# power_pcb.net
KiCad netlist of a schematic drawn in EAGLE
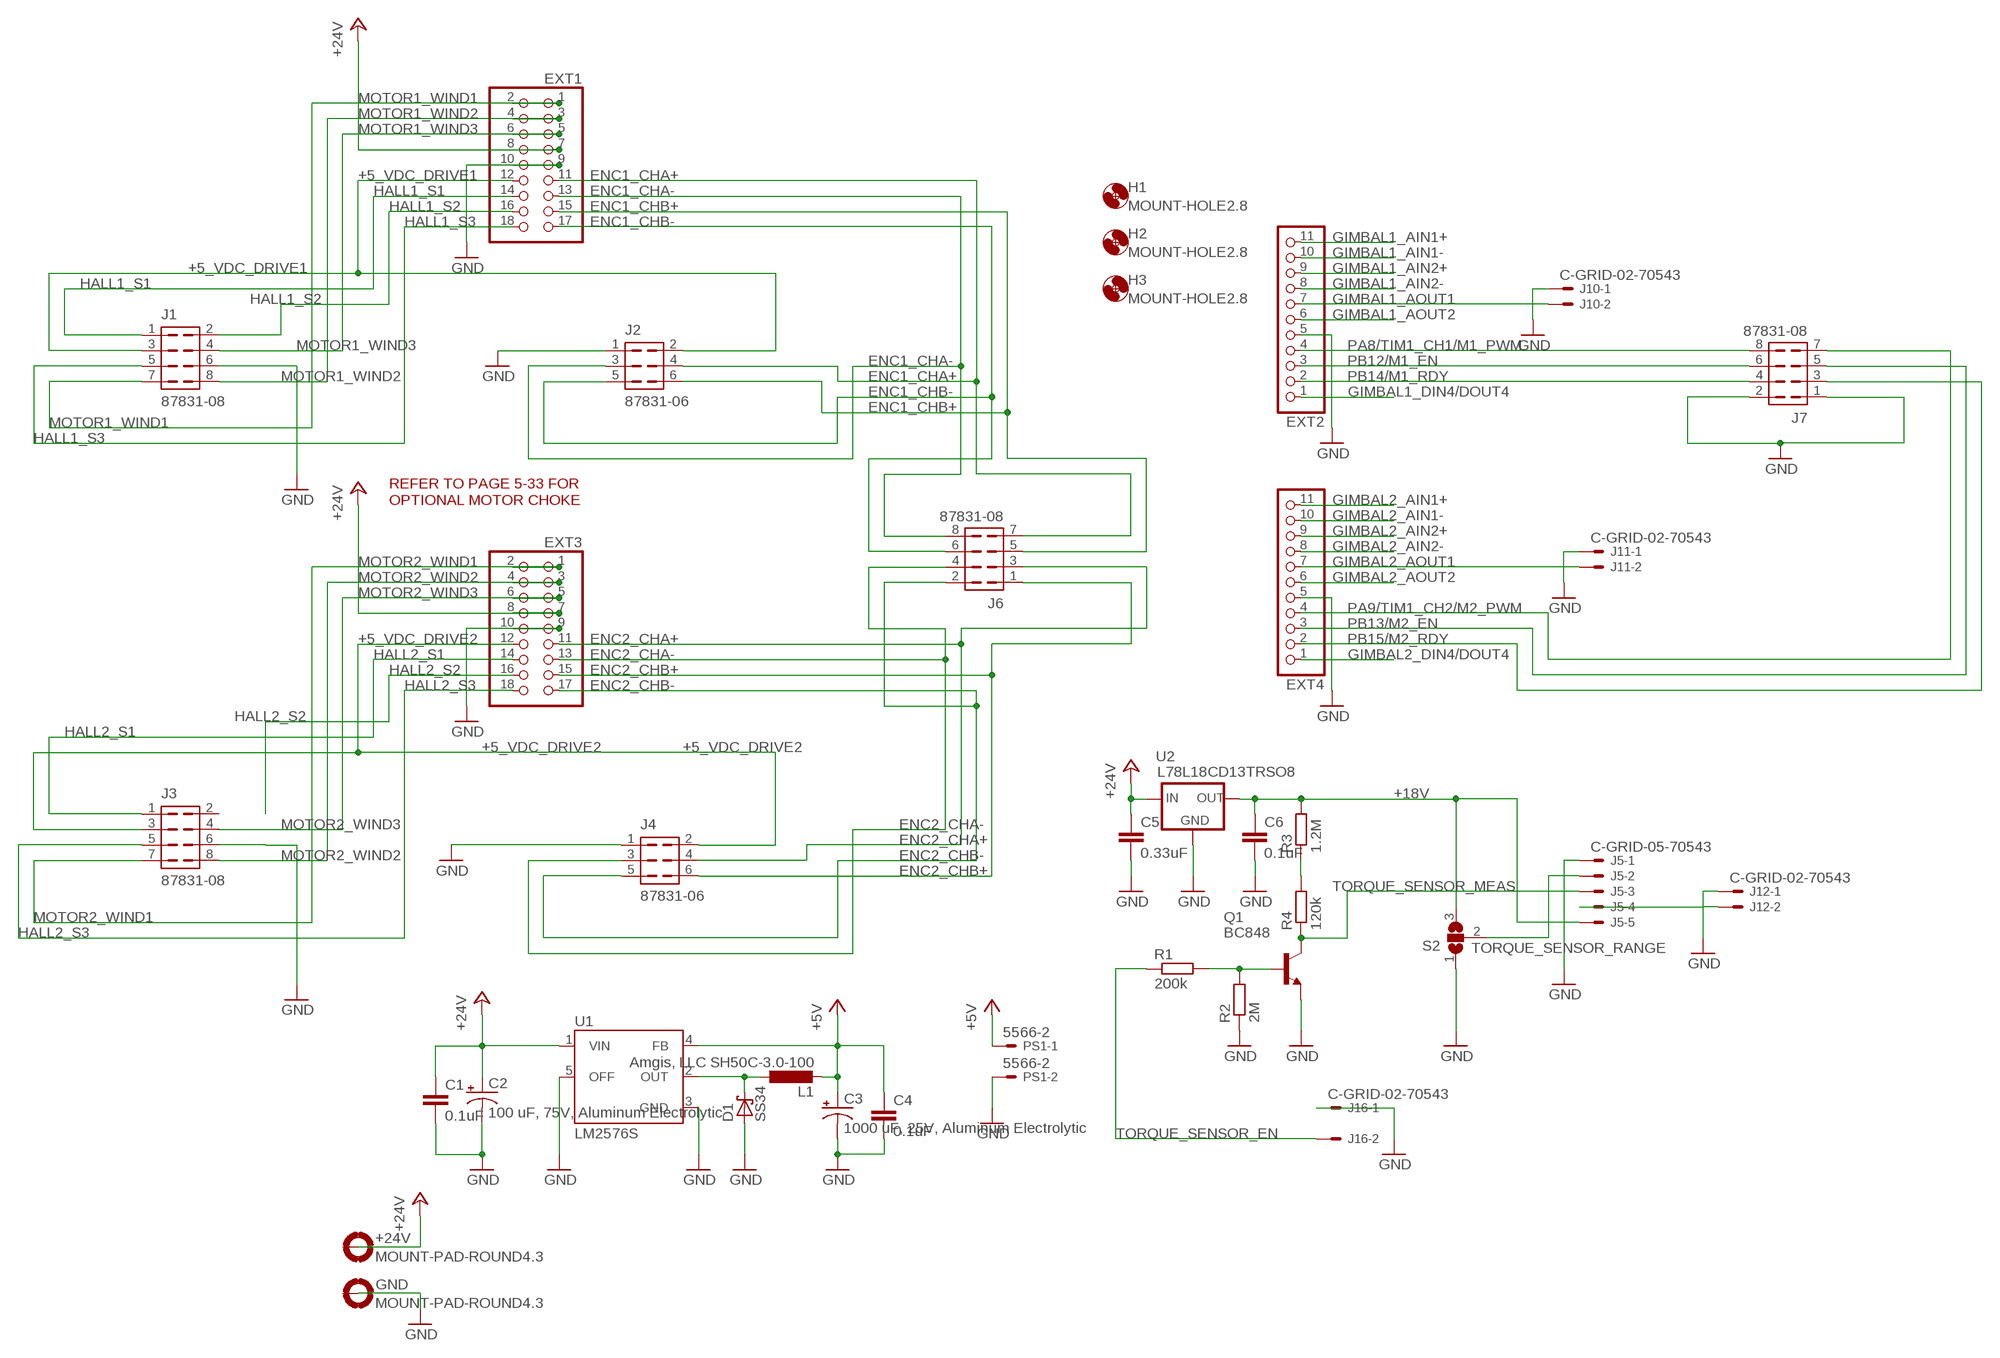
[diagram p0: schematic, sheet 1]

(export (version "E")
  (design (tool "Eeschema 10.0.6"))
  (components
    (comp (ref "+24V")
      (value "MOUNT-PAD-ROUND4.3")
      (footprint "eagle-import:4,3-PAD")
      (libsource (lib "eagle-import") (part "MOUNT-PAD-ROUND4.3"))
    )
    (comp (ref "C1")
      (value "0.1uF")
      (footprint "eagle-import:C0603")
      (libsource (lib "eagle-import") (part "C-EUC0603"))
    )
    (comp (ref "C2")
      (value "100 uF, 75V, Aluminum Electrolytic")
      (footprint "eagle-import:PANASONIC_H13")
      (libsource (lib "eagle-import") (part "CAP_POLH13"))
    )
    (comp (ref "C3")
      (value "1000 uF, 25V, Aluminum Electrolytic")
      (footprint "eagle-import:PANASONIC_H13")
      (libsource (lib "eagle-import") (part "CAP_POLH13"))
    )
    (comp (ref "C4")
      (value "0.1uF")
      (footprint "eagle-import:C0603")
      (libsource (lib "eagle-import") (part "C-EUC0603"))
    )
    (comp (ref "C5")
      (value "0.33uF")
      (footprint "eagle-import:C0603")
      (libsource (lib "eagle-import") (part "C-EUC0603"))
    )
    (comp (ref "C6")
      (value "0.1uF")
      (footprint "eagle-import:C0603")
      (libsource (lib "eagle-import") (part "C-EUC0603"))
    )
    (comp (ref "D1")
      (value "SS34")
      (footprint "eagle-import:SMC")
      (libsource (lib "eagle-import") (part "SCHOTTKY-DIODESMC"))
    )
    (comp (ref "EXT1")
      (value "PINHD-2X9")
      (footprint "eagle-import:2X09")
      (libsource (lib "eagle-import") (part "PINHD-2X9"))
    )
    (comp (ref "EXT2")
      (value "PINHD-1X11")
      (footprint "eagle-import:1X11")
      (libsource (lib "eagle-import") (part "PINHD-1X11"))
    )
    (comp (ref "EXT3")
      (value "PINHD-2X9")
      (footprint "eagle-import:2X09")
      (libsource (lib "eagle-import") (part "PINHD-2X9"))
    )
    (comp (ref "EXT4")
      (value "PINHD-1X11")
      (footprint "eagle-import:1X11")
      (libsource (lib "eagle-import") (part "PINHD-1X11"))
    )
    (comp (ref "GND")
      (value "MOUNT-PAD-ROUND4.3")
      (footprint "eagle-import:4,3-PAD")
      (libsource (lib "eagle-import") (part "MOUNT-PAD-ROUND4.3"))
    )
    (comp (ref "H1")
      (value "MOUNT-HOLE2.8")
      (footprint "eagle-import:2,8")
      (libsource (lib "eagle-import") (part "MOUNT-HOLE2.8"))
    )
    (comp (ref "H2")
      (value "MOUNT-HOLE2.8")
      (footprint "eagle-import:2,8")
      (libsource (lib "eagle-import") (part "MOUNT-HOLE2.8"))
    )
    (comp (ref "H3")
      (value "MOUNT-HOLE2.8")
      (footprint "eagle-import:2,8")
      (libsource (lib "eagle-import") (part "MOUNT-HOLE2.8"))
    )
    (comp (ref "J1")
      (value "87831-08")
      (footprint "eagle-import:87831-08")
      (libsource (lib "eagle-import") (part "87831-08"))
    )
    (comp (ref "J2")
      (value "87831-06")
      (footprint "eagle-import:87831-06")
      (libsource (lib "eagle-import") (part "87831-06"))
    )
    (comp (ref "J3")
      (value "87831-08")
      (footprint "eagle-import:87831-08")
      (libsource (lib "eagle-import") (part "87831-08"))
    )
    (comp (ref "J4")
      (value "87831-06")
      (footprint "eagle-import:87831-06")
      (libsource (lib "eagle-import") (part "87831-06"))
    )
    (comp (ref "J5")
      (value "C-GRID-05-70543")
      (footprint "eagle-import:70543-05")
      (libsource (lib "eagle-import") (part "C-GRID-05-70543"))
    )
    (comp (ref "J6")
      (value "87831-08")
      (footprint "eagle-import:87831-08")
      (libsource (lib "eagle-import") (part "87831-08"))
    )
    (comp (ref "J7")
      (value "87831-08")
      (footprint "eagle-import:87831-08")
      (libsource (lib "eagle-import") (part "87831-08"))
    )
    (comp (ref "J10")
      (value "C-GRID-02-70543")
      (footprint "eagle-import:70543-02")
      (libsource (lib "eagle-import") (part "C-GRID-02-70543"))
    )
    (comp (ref "J11")
      (value "C-GRID-02-70543")
      (footprint "eagle-import:70543-02")
      (libsource (lib "eagle-import") (part "C-GRID-02-70543"))
    )
    (comp (ref "J12")
      (value "C-GRID-02-70543")
      (footprint "eagle-import:70543-02")
      (libsource (lib "eagle-import") (part "C-GRID-02-70543"))
    )
    (comp (ref "J16")
      (value "C-GRID-02-70543")
      (footprint "eagle-import:70543-02")
      (libsource (lib "eagle-import") (part "C-GRID-02-70543"))
    )
    (comp (ref "L1")
      (value "Amgis, LLC SH50C-3.0-100")
      (footprint "eagle-import:SH50C-C4")
      (libsource (lib "eagle-import") (part "SH50CC4"))
    )
    (comp (ref "PS1")
      (value "5566-2")
      (footprint "eagle-import:5566-2")
      (libsource (lib "eagle-import") (part "5566-2"))
    )
    (comp (ref "Q1")
      (value "BC848")
      (footprint "eagle-import:SOT23")
      (libsource (lib "eagle-import") (part "BC848"))
    )
    (comp (ref "R1")
      (value "200k")
      (footprint "eagle-import:R0603")
      (libsource (lib "eagle-import") (part "R-EU_R0603"))
    )
    (comp (ref "R2")
      (value "2M")
      (footprint "eagle-import:R0603")
      (libsource (lib "eagle-import") (part "R-EU_R0603"))
    )
    (comp (ref "R3")
      (value "1.2M")
      (footprint "eagle-import:R1210")
      (libsource (lib "eagle-import") (part "R-EU_R1210"))
    )
    (comp (ref "R4")
      (value "120k")
      (footprint "eagle-import:R1210")
      (libsource (lib "eagle-import") (part "R-EU_R1210"))
    )
    (comp (ref "S2")
      (value "SJ2W")
      (footprint "eagle-import:SJ_2")
      (libsource (lib "eagle-import") (part "SJ2W"))
    )
    (comp (ref "U1")
      (value "LM2576S")
      (footprint "eagle-import:TO263-5")
      (libsource (lib "eagle-import") (part "LM2576S"))
    )
    (comp (ref "U2")
      (value "L78L18CD13TRSO8")
      (footprint "eagle-import:SO8-VREG")
      (libsource (lib "eagle-import") (part "L78L18CD13TRSO8"))
    )
  )
  (nets
    (net (code "1") (name "+5V") (class "Default")
      (node (ref "C3") (pin "+") (pinfunction "+_+") (pintype "passive"))
      (node (ref "C4") (pin "1") (pinfunction "1_1") (pintype "passive"))
      (node (ref "L1") (pin "P$2") (pinfunction "2_P$2") (pintype "passive"))
      (node (ref "PS1") (pin "1") (pinfunction "S_1") (pintype "passive"))
      (node (ref "U1") (pin "4") (pinfunction "FB_4") (pintype "input"))
    )
    (net (code "2") (name "+24V") (class "Default")
      (node (ref "C1") (pin "1") (pinfunction "1_1") (pintype "passive"))
      (node (ref "C2") (pin "+") (pinfunction "+_+") (pintype "passive"))
      (node (ref "C5") (pin "1") (pinfunction "1_1") (pintype "passive"))
      (node (ref "EXT1") (pin "7") (pinfunction "7_7") (pintype "passive"))
      (node (ref "EXT1") (pin "8") (pinfunction "8_8") (pintype "passive"))
      (node (ref "EXT3") (pin "7") (pinfunction "7_7") (pintype "passive"))
      (node (ref "EXT3") (pin "8") (pinfunction "8_8") (pintype "passive"))
      (node (ref "U1") (pin "1") (pinfunction "VIN_1") (pintype "power_in"))
      (node (ref "U2") (pin "8") (pinfunction "IN_8") (pintype "input"))
    )
    (net (code "3") (name "/+5_VDC_DRIVE1") (class "Default")
      (node (ref "EXT1") (pin "12") (pinfunction "12_12") (pintype "passive"))
      (node (ref "J1") (pin "3") (pinfunction "3_3") (pintype "passive"))
      (node (ref "J2") (pin "2") (pinfunction "2_2") (pintype "passive"))
    )
    (net (code "4") (name "/+5_VDC_DRIVE2") (class "Default")
      (node (ref "EXT3") (pin "12") (pinfunction "12_12") (pintype "passive"))
      (node (ref "J3") (pin "3") (pinfunction "3_3") (pintype "passive"))
      (node (ref "J4") (pin "2") (pinfunction "2_2") (pintype "passive"))
    )
    (net (code "5") (name "/+18V") (class "Default")
      (node (ref "C6") (pin "1") (pinfunction "1_1") (pintype "passive"))
      (node (ref "J5") (pin "5") (pinfunction "S_5") (pintype "passive"))
      (node (ref "R3") (pin "2") (pinfunction "2_2") (pintype "passive"))
      (node (ref "S2") (pin "3") (pinfunction "3_3") (pintype "passive"))
      (node (ref "U2") (pin "1") (pinfunction "OUT_1") (pintype "passive"))
    )
    (net (code "6") (name "/ENC1_CHA+") (class "Default")
      (node (ref "EXT1") (pin "11") (pinfunction "11_11") (pintype "passive"))
      (node (ref "J2") (pin "4") (pinfunction "4_4") (pintype "passive"))
      (node (ref "J6") (pin "7") (pinfunction "7_7") (pintype "passive"))
    )
    (net (code "7") (name "/ENC1_CHA-") (class "Default")
      (node (ref "EXT1") (pin "13") (pinfunction "13_13") (pintype "passive"))
      (node (ref "J2") (pin "3") (pinfunction "3_3") (pintype "passive"))
      (node (ref "J6") (pin "8") (pinfunction "8_8") (pintype "passive"))
    )
    (net (code "8") (name "/ENC1_CHB+") (class "Default")
      (node (ref "EXT1") (pin "15") (pinfunction "15_15") (pintype "passive"))
      (node (ref "J2") (pin "6") (pinfunction "6_6") (pintype "passive"))
      (node (ref "J6") (pin "5") (pinfunction "5_5") (pintype "passive"))
    )
    (net (code "9") (name "/ENC1_CHB-") (class "Default")
      (node (ref "EXT1") (pin "17") (pinfunction "17_17") (pintype "passive"))
      (node (ref "J2") (pin "5") (pinfunction "5_5") (pintype "passive"))
      (node (ref "J6") (pin "6") (pinfunction "6_6") (pintype "passive"))
    )
    (net (code "10") (name "/ENC2_CHA+") (class "Default")
      (node (ref "EXT3") (pin "11") (pinfunction "11_11") (pintype "passive"))
      (node (ref "J4") (pin "4") (pinfunction "4_4") (pintype "passive"))
      (node (ref "J6") (pin "3") (pinfunction "3_3") (pintype "passive"))
    )
    (net (code "11") (name "/ENC2_CHA-") (class "Default")
      (node (ref "EXT3") (pin "13") (pinfunction "13_13") (pintype "passive"))
      (node (ref "J4") (pin "3") (pinfunction "3_3") (pintype "passive"))
      (node (ref "J6") (pin "4") (pinfunction "4_4") (pintype "passive"))
    )
    (net (code "12") (name "/ENC2_CHB+") (class "Default")
      (node (ref "EXT3") (pin "15") (pinfunction "15_15") (pintype "passive"))
      (node (ref "J4") (pin "6") (pinfunction "6_6") (pintype "passive"))
      (node (ref "J6") (pin "1") (pinfunction "1_1") (pintype "passive"))
    )
    (net (code "13") (name "/ENC2_CHB-") (class "Default")
      (node (ref "EXT3") (pin "17") (pinfunction "17_17") (pintype "passive"))
      (node (ref "J4") (pin "5") (pinfunction "5_5") (pintype "passive"))
      (node (ref "J6") (pin "2") (pinfunction "2_2") (pintype "passive"))
    )
    (net (code "14") (name "/GIMBAL1_AIN1+") (class "Default")
      (node (ref "EXT2") (pin "11") (pinfunction "11_11") (pintype "passive"))
    )
    (net (code "15") (name "/GIMBAL1_AIN1-") (class "Default")
      (node (ref "EXT2") (pin "10") (pinfunction "10_10") (pintype "passive"))
    )
    (net (code "16") (name "/GIMBAL1_AIN2+") (class "Default")
      (node (ref "EXT2") (pin "9") (pinfunction "9_9") (pintype "passive"))
    )
    (net (code "17") (name "/GIMBAL1_AIN2-") (class "Default")
      (node (ref "EXT2") (pin "8") (pinfunction "8_8") (pintype "passive"))
    )
    (net (code "18") (name "/GIMBAL1_AOUT1") (class "Default")
      (node (ref "EXT2") (pin "7") (pinfunction "7_7") (pintype "passive"))
      (node (ref "J10") (pin "2") (pinfunction "S_2") (pintype "passive"))
    )
    (net (code "19") (name "/GIMBAL1_AOUT2") (class "Default")
      (node (ref "EXT2") (pin "6") (pinfunction "6_6") (pintype "passive"))
    )
    (net (code "20") (name "/GIMBAL1_DIN4{slash}DOUT4") (class "Default")
      (node (ref "EXT2") (pin "1") (pinfunction "1_1") (pintype "passive"))
    )
    (net (code "21") (name "/GIMBAL2_AIN1+") (class "Default")
      (node (ref "EXT4") (pin "11") (pinfunction "11_11") (pintype "passive"))
    )
    (net (code "22") (name "/GIMBAL2_AIN1-") (class "Default")
      (node (ref "EXT4") (pin "10") (pinfunction "10_10") (pintype "passive"))
    )
    (net (code "23") (name "/GIMBAL2_AIN2+") (class "Default")
      (node (ref "EXT4") (pin "9") (pinfunction "9_9") (pintype "passive"))
    )
    (net (code "24") (name "/GIMBAL2_AIN2-") (class "Default")
      (node (ref "EXT4") (pin "8") (pinfunction "8_8") (pintype "passive"))
    )
    (net (code "25") (name "/GIMBAL2_AOUT1") (class "Default")
      (node (ref "EXT4") (pin "7") (pinfunction "7_7") (pintype "passive"))
      (node (ref "J11") (pin "2") (pinfunction "S_2") (pintype "passive"))
    )
    (net (code "26") (name "/GIMBAL2_AOUT2") (class "Default")
      (node (ref "EXT4") (pin "6") (pinfunction "6_6") (pintype "passive"))
    )
    (net (code "27") (name "/GIMBAL2_DIN4{slash}DOUT4") (class "Default")
      (node (ref "EXT4") (pin "1") (pinfunction "1_1") (pintype "passive"))
    )
    (net (code "28") (name "/HALL1_S1") (class "Default")
      (node (ref "EXT1") (pin "14") (pinfunction "14_14") (pintype "passive"))
      (node (ref "J1") (pin "1") (pinfunction "1_1") (pintype "passive"))
    )
    (net (code "29") (name "/HALL1_S2") (class "Default")
      (node (ref "EXT1") (pin "16") (pinfunction "16_16") (pintype "passive"))
      (node (ref "J1") (pin "2") (pinfunction "2_2") (pintype "passive"))
    )
    (net (code "30") (name "/HALL1_S3") (class "Default")
      (node (ref "EXT1") (pin "18") (pinfunction "18_18") (pintype "passive"))
      (node (ref "J1") (pin "5") (pinfunction "5_5") (pintype "passive"))
    )
    (net (code "31") (name "/HALL2_S1") (class "Default")
      (node (ref "EXT3") (pin "14") (pinfunction "14_14") (pintype "passive"))
      (node (ref "J3") (pin "1") (pinfunction "1_1") (pintype "passive"))
    )
    (net (code "32") (name "/HALL2_S2") (class "Default")
      (node (ref "EXT3") (pin "16") (pinfunction "16_16") (pintype "passive"))
    )
    (net (code "33") (name "/HALL2_S3") (class "Default")
      (node (ref "EXT3") (pin "18") (pinfunction "18_18") (pintype "passive"))
      (node (ref "J3") (pin "5") (pinfunction "5_5") (pintype "passive"))
    )
    (net (code "34") (name "/MOTOR1_WIND1") (class "Default")
      (node (ref "EXT1") (pin "1") (pinfunction "1_1") (pintype "passive"))
      (node (ref "EXT1") (pin "2") (pinfunction "2_2") (pintype "passive"))
      (node (ref "J1") (pin "7") (pinfunction "7_7") (pintype "passive"))
    )
    (net (code "35") (name "/MOTOR1_WIND2") (class "Default")
      (node (ref "EXT1") (pin "3") (pinfunction "3_3") (pintype "passive"))
      (node (ref "EXT1") (pin "4") (pinfunction "4_4") (pintype "passive"))
      (node (ref "J1") (pin "8") (pinfunction "8_8") (pintype "passive"))
    )
    (net (code "36") (name "/MOTOR1_WIND3") (class "Default")
      (node (ref "EXT1") (pin "5") (pinfunction "5_5") (pintype "passive"))
      (node (ref "EXT1") (pin "6") (pinfunction "6_6") (pintype "passive"))
      (node (ref "J1") (pin "4") (pinfunction "4_4") (pintype "passive"))
    )
    (net (code "37") (name "/MOTOR2_WIND1") (class "Default")
      (node (ref "EXT3") (pin "1") (pinfunction "1_1") (pintype "passive"))
      (node (ref "EXT3") (pin "2") (pinfunction "2_2") (pintype "passive"))
      (node (ref "J3") (pin "7") (pinfunction "7_7") (pintype "passive"))
    )
    (net (code "38") (name "/MOTOR2_WIND2") (class "Default")
      (node (ref "EXT3") (pin "3") (pinfunction "3_3") (pintype "passive"))
      (node (ref "EXT3") (pin "4") (pinfunction "4_4") (pintype "passive"))
      (node (ref "J3") (pin "8") (pinfunction "8_8") (pintype "passive"))
    )
    (net (code "39") (name "/MOTOR2_WIND3") (class "Default")
      (node (ref "EXT3") (pin "5") (pinfunction "5_5") (pintype "passive"))
      (node (ref "EXT3") (pin "6") (pinfunction "6_6") (pintype "passive"))
      (node (ref "J3") (pin "4") (pinfunction "4_4") (pintype "passive"))
    )
    (net (code "40") (name "/PA8{slash}TIM1_CH1{slash}M1_PWM") (class "Default")
      (node (ref "EXT2") (pin "4") (pinfunction "4_4") (pintype "passive"))
      (node (ref "J7") (pin "8") (pinfunction "8_8") (pintype "passive"))
    )
    (net (code "41") (name "/PA9{slash}TIM1_CH2{slash}M2_PWM") (class "Default")
      (node (ref "EXT4") (pin "4") (pinfunction "4_4") (pintype "passive"))
      (node (ref "J7") (pin "7") (pinfunction "7_7") (pintype "passive"))
    )
    (net (code "42") (name "/PB12{slash}M1_EN") (class "Default")
      (node (ref "EXT2") (pin "3") (pinfunction "3_3") (pintype "passive"))
      (node (ref "J7") (pin "6") (pinfunction "6_6") (pintype "passive"))
    )
    (net (code "43") (name "/PB13{slash}M2_EN") (class "Default")
      (node (ref "EXT4") (pin "3") (pinfunction "3_3") (pintype "passive"))
      (node (ref "J7") (pin "5") (pinfunction "5_5") (pintype "passive"))
    )
    (net (code "44") (name "/PB14{slash}M1_RDY") (class "Default")
      (node (ref "EXT2") (pin "2") (pinfunction "2_2") (pintype "passive"))
      (node (ref "J7") (pin "4") (pinfunction "4_4") (pintype "passive"))
    )
    (net (code "45") (name "/PB15{slash}M2_RDY") (class "Default")
      (node (ref "EXT4") (pin "2") (pinfunction "2_2") (pintype "passive"))
      (node (ref "J7") (pin "3") (pinfunction "3_3") (pintype "passive"))
    )
    (net (code "46") (name "/TORQUE_SENSOR_EN") (class "Default")
      (node (ref "J16") (pin "2") (pinfunction "S_2") (pintype "passive"))
      (node (ref "R1") (pin "1") (pinfunction "1_1") (pintype "passive"))
    )
    (net (code "47") (name "/TORQUE_SENSOR_MEAS") (class "Default")
      (node (ref "J5") (pin "3") (pinfunction "S_3") (pintype "passive"))
      (node (ref "Q1") (pin "3") (pinfunction "C_3") (pintype "passive"))
      (node (ref "R4") (pin "1") (pinfunction "1_1") (pintype "passive"))
    )
    (net (code "48") (name "/TORQUE_SENSOR_RANGE") (class "Default")
      (node (ref "J5") (pin "2") (pinfunction "S_2") (pintype "passive"))
      (node (ref "S2") (pin "2") (pinfunction "2_2") (pintype "passive"))
    )
    (net (code "49") (name "GND") (class "Default")
      (node (ref "C1") (pin "2") (pinfunction "2_2") (pintype "passive"))
      (node (ref "C2") (pin "-") (pinfunction "-_-") (pintype "passive"))
      (node (ref "C3") (pin "-") (pinfunction "-_-") (pintype "passive"))
      (node (ref "C4") (pin "2") (pinfunction "2_2") (pintype "passive"))
      (node (ref "C5") (pin "2") (pinfunction "2_2") (pintype "passive"))
      (node (ref "C6") (pin "2") (pinfunction "2_2") (pintype "passive"))
      (node (ref "D1") (pin "A") (pinfunction "A_A") (pintype "passive"))
      (node (ref "EXT1") (pin "10") (pinfunction "10_10") (pintype "passive"))
      (node (ref "EXT1") (pin "9") (pinfunction "9_9") (pintype "passive"))
      (node (ref "EXT2") (pin "5") (pinfunction "5_5") (pintype "passive"))
      (node (ref "EXT3") (pin "10") (pinfunction "10_10") (pintype "passive"))
      (node (ref "EXT3") (pin "9") (pinfunction "9_9") (pintype "passive"))
      (node (ref "EXT4") (pin "5") (pinfunction "5_5") (pintype "passive"))
      (node (ref "J1") (pin "6") (pinfunction "6_6") (pintype "passive"))
      (node (ref "J10") (pin "1") (pinfunction "S_1") (pintype "passive"))
      (node (ref "J11") (pin "1") (pinfunction "S_1") (pintype "passive"))
      (node (ref "J12") (pin "1") (pinfunction "S_1") (pintype "passive"))
      (node (ref "J16") (pin "1") (pinfunction "S_1") (pintype "passive"))
      (node (ref "J2") (pin "1") (pinfunction "1_1") (pintype "passive"))
      (node (ref "J3") (pin "6") (pinfunction "6_6") (pintype "passive"))
      (node (ref "J4") (pin "1") (pinfunction "1_1") (pintype "passive"))
      (node (ref "J5") (pin "1") (pinfunction "S_1") (pintype "passive"))
      (node (ref "J7") (pin "1") (pinfunction "1_1") (pintype "passive"))
      (node (ref "J7") (pin "2") (pinfunction "2_2") (pintype "passive"))
      (node (ref "PS1") (pin "2") (pinfunction "S_2") (pintype "passive"))
      (node (ref "Q1") (pin "2") (pinfunction "E_2") (pintype "passive"))
      (node (ref "R2") (pin "1") (pinfunction "1_1") (pintype "passive"))
      (node (ref "S2") (pin "1") (pinfunction "1_1") (pintype "passive"))
      (node (ref "U1") (pin "3") (pinfunction "GND_3") (pintype "power_in"))
      (node (ref "U1") (pin "5") (pinfunction "OFF_5") (pintype "input"))
      (node (ref "U2") (pin "2") (pinfunction "GND_2") (pintype "input"))
      (node (ref "U2") (pin "3") (pinfunction "GND_3") (pintype "input"))
      (node (ref "U2") (pin "6") (pinfunction "GND_6") (pintype "input"))
      (node (ref "U2") (pin "7") (pinfunction "GND_7") (pintype "input"))
    )
    (net (code "50") (name "Net-(J12B-S)") (class "Default")
      (node (ref "J12") (pin "2") (pinfunction "S_2") (pintype "passive"))
      (node (ref "J5") (pin "4") (pinfunction "S_4") (pintype "passive"))
    )
    (net (code "51") (name "Net-(L1-1)") (class "Default")
      (node (ref "D1") (pin "C") (pinfunction "C_C") (pintype "passive"))
      (node (ref "L1") (pin "P$1") (pinfunction "1_P$1") (pintype "passive"))
      (node (ref "U1") (pin "2") (pinfunction "OUT_2") (pintype "output"))
    )
    (net (code "52") (name "Net-(Q1-B)") (class "Default")
      (node (ref "Q1") (pin "1") (pinfunction "B_1") (pintype "passive"))
      (node (ref "R1") (pin "2") (pinfunction "2_2") (pintype "passive"))
      (node (ref "R2") (pin "2") (pinfunction "2_2") (pintype "passive"))
    )
    (net (code "53") (name "Net-(R3-Pad1)") (class "Default")
      (node (ref "R3") (pin "1") (pinfunction "1_1") (pintype "passive"))
      (node (ref "R4") (pin "2") (pinfunction "2_2") (pintype "passive"))
    )
    (net (code "54") (name "unconnected-(+24V-MOUNT-PadB4,3)") (class "Default")
      (node (ref "+24V") (pin "B4,3") (pinfunction "MOUNT_B4,3") (pintype "passive"))
    )
    (net (code "55") (name "unconnected-(GND-MOUNT-PadB4,3)") (class "Default")
      (node (ref "GND") (pin "B4,3") (pinfunction "MOUNT_B4,3") (pintype "passive"))
    )
    (net (code "56") (name "unconnected-(J3-Pad2)") (class "Default")
      (node (ref "J3") (pin "2") (pinfunction "2_2") (pintype "passive"))
    )
  )
)
